# power.net
KiCad netlist of a schematic drawn in Altium Designer
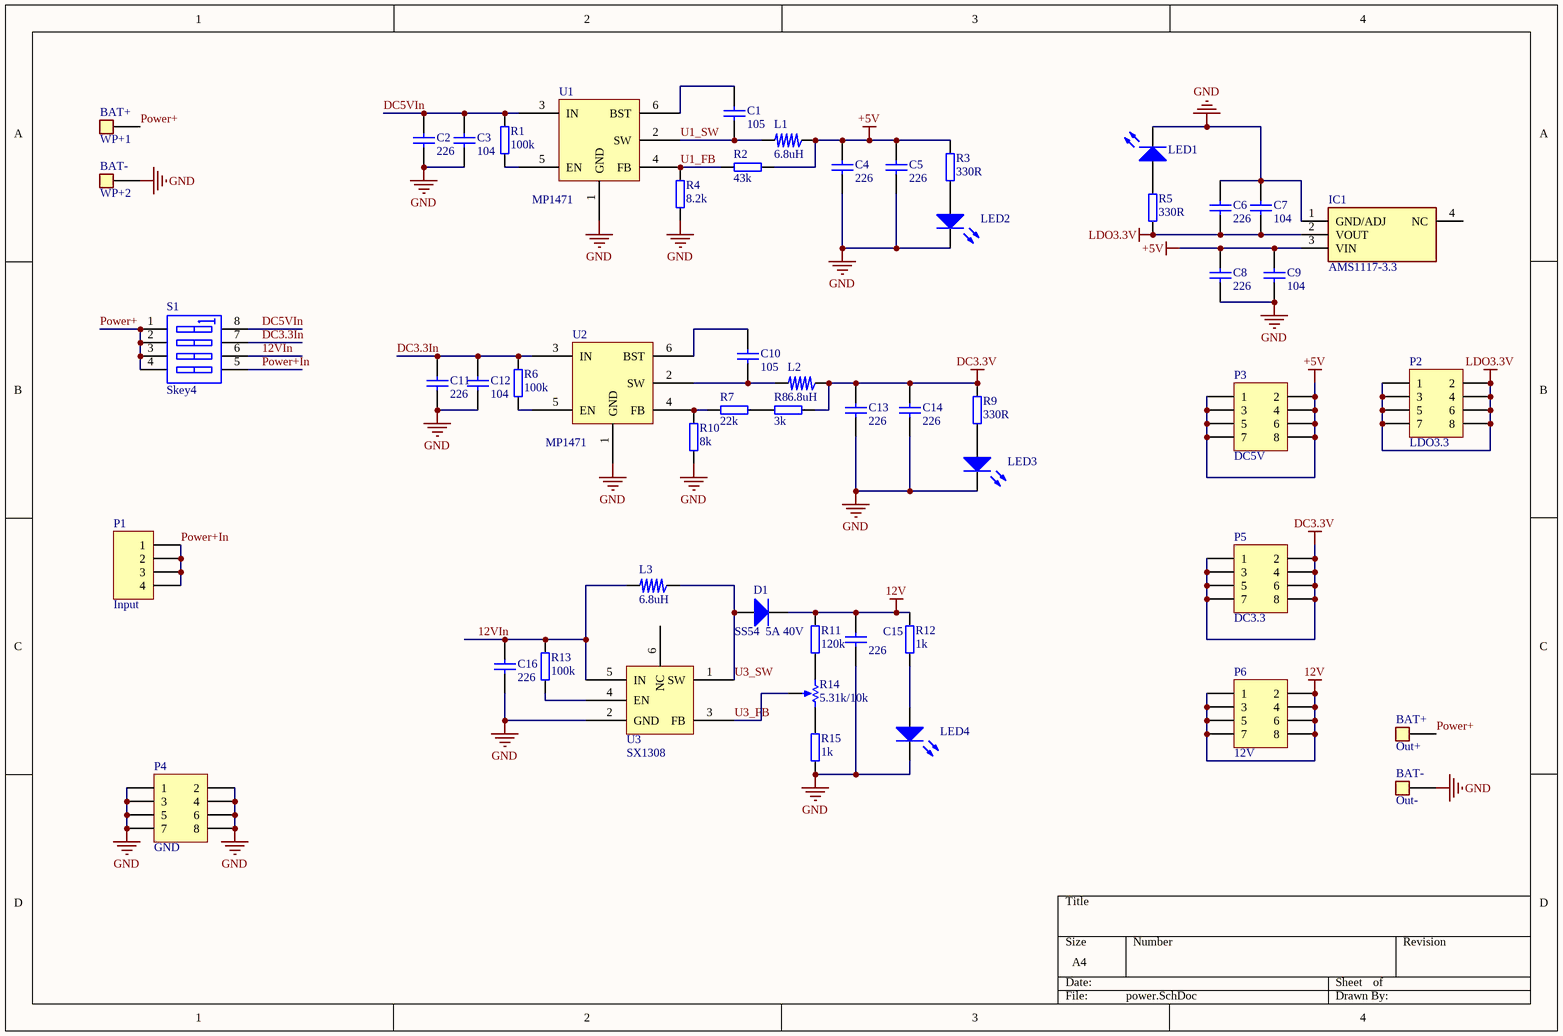
[diagram p0: power.SchDoc]

(export (version "E")
  (design (tool "Eeschema 10.0.6"))
  (components
    (comp (ref "C1")
      (value "105")
      (footprint "CAPC1608[0603]")
      (description "Chip Capacitor, PSpice Model")
      (fields
        (field (name "TOLERANCE") "Y5V")
        (field (name "VOLTAGE") "3V")
        (field (name "PUBLISHER") "Altium Limited")
      )
      (libsource (lib "!)Miscellaneous Integrated Library") (part "Cap Chip 1"))
    )
    (comp (ref "C2")
      (value "226")
      (footprint "CAPC1608[0603]")
      (description "Chip Capacitor, PSpice Model")
      (fields
        (field (name "TOLERANCE") "Y5V")
        (field (name "VOLTAGE") "3V")
        (field (name "PUBLISHER") "Altium Limited")
      )
      (libsource (lib "!)Miscellaneous Integrated Library") (part "Cap Chip 1"))
    )
    (comp (ref "C3")
      (value "104")
      (footprint "CAPC1608[0603]")
      (description "Chip Capacitor, PSpice Model")
      (fields
        (field (name "TOLERANCE") "Y5V")
        (field (name "VOLTAGE") "3V")
        (field (name "PUBLISHER") "Altium Limited")
      )
      (libsource (lib "!)Miscellaneous Integrated Library") (part "Cap Chip 1"))
    )
    (comp (ref "C4")
      (value "226")
      (footprint "CAPC1608[0603]")
      (description "Chip Capacitor, PSpice Model")
      (fields
        (field (name "TOLERANCE") "Y5V")
        (field (name "VOLTAGE") "3V")
        (field (name "PUBLISHER") "Altium Limited")
      )
      (libsource (lib "!)Miscellaneous Integrated Library") (part "Cap Chip 1"))
    )
    (comp (ref "C5")
      (value "226")
      (footprint "CAPC1608[0603]")
      (description "Chip Capacitor, PSpice Model")
      (fields
        (field (name "TOLERANCE") "Y5V")
        (field (name "VOLTAGE") "3V")
        (field (name "PUBLISHER") "Altium Limited")
      )
      (libsource (lib "!)Miscellaneous Integrated Library") (part "Cap Chip 1"))
    )
    (comp (ref "C6")
      (value "226")
      (footprint "CAPC1608[0603]")
      (description "Chip Capacitor, PSpice Model")
      (fields
        (field (name "TOLERANCE") "Y5V")
        (field (name "VOLTAGE") "3V")
        (field (name "PUBLISHER") "Altium Limited")
      )
      (libsource (lib "!)Miscellaneous Integrated Library") (part "Cap Chip 1"))
    )
    (comp (ref "C7")
      (value "104")
      (footprint "CAPC1608[0603]")
      (description "Chip Capacitor, PSpice Model")
      (fields
        (field (name "TOLERANCE") "Y5V")
        (field (name "VOLTAGE") "3V")
        (field (name "PUBLISHER") "Altium Limited")
      )
      (libsource (lib "!)Miscellaneous Integrated Library") (part "Cap Chip 1"))
    )
    (comp (ref "C8")
      (value "226")
      (footprint "CAPC1608[0603]")
      (description "Chip Capacitor, PSpice Model")
      (fields
        (field (name "TOLERANCE") "Y5V")
        (field (name "VOLTAGE") "3V")
        (field (name "PUBLISHER") "Altium Limited")
      )
      (libsource (lib "!)Miscellaneous Integrated Library") (part "Cap Chip 1"))
    )
    (comp (ref "C9")
      (value "104")
      (footprint "CAPC1608[0603]")
      (description "Chip Capacitor, PSpice Model")
      (fields
        (field (name "TOLERANCE") "Y5V")
        (field (name "VOLTAGE") "3V")
        (field (name "PUBLISHER") "Altium Limited")
      )
      (libsource (lib "!)Miscellaneous Integrated Library") (part "Cap Chip 1"))
    )
    (comp (ref "C10")
      (value "105")
      (footprint "CAPC1608[0603]")
      (description "Chip Capacitor, PSpice Model")
      (fields
        (field (name "TOLERANCE") "Y5V")
        (field (name "VOLTAGE") "3V")
        (field (name "PUBLISHER") "Altium Limited")
      )
      (libsource (lib "!)Miscellaneous Integrated Library") (part "Cap Chip 1"))
    )
    (comp (ref "C11")
      (value "226")
      (footprint "CAPC1608[0603]")
      (description "Chip Capacitor, PSpice Model")
      (fields
        (field (name "TOLERANCE") "Y5V")
        (field (name "VOLTAGE") "3V")
        (field (name "PUBLISHER") "Altium Limited")
      )
      (libsource (lib "!)Miscellaneous Integrated Library") (part "Cap Chip 1"))
    )
    (comp (ref "C12")
      (value "104")
      (footprint "CAPC1608[0603]")
      (description "Chip Capacitor, PSpice Model")
      (fields
        (field (name "TOLERANCE") "Y5V")
        (field (name "VOLTAGE") "3V")
        (field (name "PUBLISHER") "Altium Limited")
      )
      (libsource (lib "!)Miscellaneous Integrated Library") (part "Cap Chip 1"))
    )
    (comp (ref "C13")
      (value "226")
      (footprint "CAPC1608[0603]")
      (description "Chip Capacitor, PSpice Model")
      (fields
        (field (name "TOLERANCE") "Y5V")
        (field (name "VOLTAGE") "3V")
        (field (name "PUBLISHER") "Altium Limited")
      )
      (libsource (lib "!)Miscellaneous Integrated Library") (part "Cap Chip 1"))
    )
    (comp (ref "C14")
      (value "226")
      (footprint "CAPC1608[0603]")
      (description "Chip Capacitor, PSpice Model")
      (fields
        (field (name "TOLERANCE") "Y5V")
        (field (name "VOLTAGE") "3V")
        (field (name "PUBLISHER") "Altium Limited")
      )
      (libsource (lib "!)Miscellaneous Integrated Library") (part "Cap Chip 1"))
    )
    (comp (ref "C15")
      (value "226")
      (footprint "CAPC1608[0603]")
      (description "Chip Capacitor, PSpice Model")
      (fields
        (field (name "TOLERANCE") "Y5V")
        (field (name "VOLTAGE") "3V")
        (field (name "PUBLISHER") "Altium Limited")
      )
      (libsource (lib "!)Miscellaneous Integrated Library") (part "Cap Chip 1"))
    )
    (comp (ref "C16")
      (value "226")
      (footprint "CAPC1608[0603]")
      (description "Chip Capacitor, PSpice Model")
      (fields
        (field (name "TOLERANCE") "Y5V")
        (field (name "VOLTAGE") "3V")
        (field (name "PUBLISHER") "Altium Limited")
      )
      (libsource (lib "!)Miscellaneous Integrated Library") (part "Cap Chip 1"))
    )
    (comp (ref "D1")
      (value "SS54  5A 40V")
      (footprint "SMA[DO-214AC]")
      (description "Molded Diode")
      (fields
        (field (name "PARTNUMBER") "SS54  5A 40V")
        (field (name "VOLTAGE") "5A40V")
        (field (name "PUBLISHER") "Altium Limited")
      )
      (libsource (lib "!)Miscellaneous Integrated Library") (part "Diode SMx"))
    )
    (comp (ref "IC1")
      (value "AMS1117-3.3")
      (footprint "SOT229P700X180-4N")
      (description "Integrated Circuit")
      (libsource (lib "SamacSys") (part "AMS1117-3.3"))
    )
    (comp (ref "L1") (value "6.8uH") (footprint "WHC0420") (libsource (lib "BuildDev") (part "L")))
    (comp (ref "L2") (value "6.8uH") (footprint "WHC0420") (libsource (lib "BuildDev") (part "L")))
    (comp (ref "L3") (value "6.8uH") (footprint "WHC0420") (libsource (lib "BuildDev") (part "L")))
    (comp (ref "LED1")
      (value "Red")
      (footprint "LEDC1608(0603)")
      (description "Typical Chip LED")
      (fields (field (name "PUBLISHER") "Altium Limited"))
      (libsource (lib "!)Miscellaneous Integrated Library") (part "LED Chip"))
    )
    (comp (ref "LED2")
      (value "Red")
      (footprint "LEDC1608(0603)")
      (description "Typical Chip LED")
      (fields (field (name "PUBLISHER") "Altium Limited"))
      (libsource (lib "!)Miscellaneous Integrated Library") (part "LED Chip"))
    )
    (comp (ref "LED3")
      (value "Red")
      (footprint "LEDC1608(0603)")
      (description "Typical Chip LED")
      (fields (field (name "PUBLISHER") "Altium Limited"))
      (libsource (lib "!)Miscellaneous Integrated Library") (part "LED Chip"))
    )
    (comp (ref "LED4")
      (value "Red")
      (footprint "LEDC1608(0603)")
      (description "Typical Chip LED")
      (fields (field (name "PUBLISHER") "Altium Limited"))
      (libsource (lib "!)Miscellaneous Integrated Library") (part "LED Chip"))
    )
    (comp (ref "Out+")
      (value "BAT+")
      (footprint "WirePadSingleSide")
      (description "Wire soldering pad.")
      (libsource (lib "!)Miscellaneous Integrated Library") (part "Wire Pad"))
    )
    (comp (ref "Out-")
      (value "BAT-")
      (footprint "WirePadSingleSide")
      (description "Wire soldering pad.")
      (libsource (lib "!)Miscellaneous Integrated Library") (part "Wire Pad"))
    )
    (comp (ref "P1")
      (value "Input")
      (footprint "HDR1X4")
      (description "Header, 4-Pin")
      (fields (field (name "PUBLISHER") "Altium Limited"))
      (libsource (lib "!)Miscellaneous Integrated Library") (part "Header 4"))
    )
    (comp (ref "P2")
      (value "LDO3.3")
      (footprint "HDR2X4")
      (description "Header, 4-Pin, Dual row")
      (fields (field (name "PUBLISHER") "Altium Limited"))
      (libsource (lib "!)Miscellaneous Integrated Library") (part "Header 4X2"))
    )
    (comp (ref "P3")
      (value "DC5V")
      (footprint "HDR2X4")
      (description "Header, 4-Pin, Dual row")
      (fields (field (name "PUBLISHER") "Altium Limited"))
      (libsource (lib "!)Miscellaneous Integrated Library") (part "Header 4X2"))
    )
    (comp (ref "P4")
      (value "GND")
      (footprint "HDR2X4")
      (description "Header, 4-Pin, Dual row")
      (fields (field (name "PUBLISHER") "Altium Limited"))
      (libsource (lib "!)Miscellaneous Integrated Library") (part "Header 4X2"))
    )
    (comp (ref "P5")
      (value "DC3.3")
      (footprint "HDR2X4")
      (description "Header, 4-Pin, Dual row")
      (fields (field (name "PUBLISHER") "Altium Limited"))
      (libsource (lib "!)Miscellaneous Integrated Library") (part "Header 4X2"))
    )
    (comp (ref "P6")
      (value "12V")
      (footprint "HDR2X4")
      (description "Header, 4-Pin, Dual row")
      (fields (field (name "PUBLISHER") "Altium Limited"))
      (libsource (lib "!)Miscellaneous Integrated Library") (part "Header 4X2"))
    )
    (comp (ref "R1")
      (value "100k")
      (footprint "RESC1608[0603]")
      (description "Chip Resistor, PSpice Model, IPC PCB Library Drawing")
      (fields (field (name "TOLERANCE") "5%") (field (name "PUBLISHER") "Altium Limited"))
      (libsource (lib "!)Miscellaneous Integrated Library") (part "Res Chip 2p 1"))
    )
    (comp (ref "R2")
      (value "43k")
      (footprint "RESC1608[0603]")
      (description "Chip Resistor, PSpice Model, IPC PCB Library Drawing")
      (fields (field (name "TOLERANCE") "5%") (field (name "PUBLISHER") "Altium Limited"))
      (libsource (lib "!)Miscellaneous Integrated Library") (part "Res Chip 2p 1"))
    )
    (comp (ref "R3")
      (value "330R")
      (footprint "RESC1608[0603]")
      (description "Chip Resistor, PSpice Model, IPC PCB Library Drawing")
      (fields (field (name "TOLERANCE") "5%") (field (name "PUBLISHER") "Altium Limited"))
      (libsource (lib "!)Miscellaneous Integrated Library") (part "Res Chip 2p 1"))
    )
    (comp (ref "R4")
      (value "8.2k")
      (footprint "RESC1608[0603]")
      (description "Chip Resistor, PSpice Model, IPC PCB Library Drawing")
      (fields (field (name "TOLERANCE") "5%") (field (name "PUBLISHER") "Altium Limited"))
      (libsource (lib "!)Miscellaneous Integrated Library") (part "Res Chip 2p 1"))
    )
    (comp (ref "R5")
      (value "330R")
      (footprint "RESC1608[0603]")
      (description "Chip Resistor, PSpice Model, IPC PCB Library Drawing")
      (fields (field (name "TOLERANCE") "5%") (field (name "PUBLISHER") "Altium Limited"))
      (libsource (lib "!)Miscellaneous Integrated Library") (part "Res Chip 2p 1"))
    )
    (comp (ref "R6")
      (value "100k")
      (footprint "RESC1608[0603]")
      (description "Chip Resistor, PSpice Model, IPC PCB Library Drawing")
      (fields (field (name "TOLERANCE") "5%") (field (name "PUBLISHER") "Altium Limited"))
      (libsource (lib "!)Miscellaneous Integrated Library") (part "Res Chip 2p 1"))
    )
    (comp (ref "R7")
      (value "22k")
      (footprint "RESC1608[0603]")
      (description "Chip Resistor, PSpice Model, IPC PCB Library Drawing")
      (fields (field (name "TOLERANCE") "5%") (field (name "PUBLISHER") "Altium Limited"))
      (libsource (lib "!)Miscellaneous Integrated Library") (part "Res Chip 2p 1"))
    )
    (comp (ref "R8")
      (value "3k")
      (footprint "RESC1608[0603]")
      (description "Chip Resistor, PSpice Model, IPC PCB Library Drawing")
      (fields (field (name "TOLERANCE") "5%") (field (name "PUBLISHER") "Altium Limited"))
      (libsource (lib "!)Miscellaneous Integrated Library") (part "Res Chip 2p 1"))
    )
    (comp (ref "R9")
      (value "330R")
      (footprint "RESC1608[0603]")
      (description "Chip Resistor, PSpice Model, IPC PCB Library Drawing")
      (fields (field (name "TOLERANCE") "5%") (field (name "PUBLISHER") "Altium Limited"))
      (libsource (lib "!)Miscellaneous Integrated Library") (part "Res Chip 2p 1"))
    )
    (comp (ref "R10")
      (value "8k")
      (footprint "RESC1608[0603]")
      (description "Chip Resistor, PSpice Model, IPC PCB Library Drawing")
      (fields (field (name "TOLERANCE") "5%") (field (name "PUBLISHER") "Altium Limited"))
      (libsource (lib "!)Miscellaneous Integrated Library") (part "Res Chip 2p 1"))
    )
    (comp (ref "R11")
      (value "120k")
      (footprint "RESC1608[0603]")
      (description "Chip Resistor, PSpice Model, IPC PCB Library Drawing")
      (fields (field (name "TOLERANCE") "5%") (field (name "PUBLISHER") "Altium Limited"))
      (libsource (lib "!)Miscellaneous Integrated Library") (part "Res Chip 2p 1"))
    )
    (comp (ref "R12")
      (value "1k")
      (footprint "RESC1608[0603]")
      (description "Chip Resistor, PSpice Model, IPC PCB Library Drawing")
      (fields (field (name "TOLERANCE") "5%") (field (name "PUBLISHER") "Altium Limited"))
      (libsource (lib "!)Miscellaneous Integrated Library") (part "Res Chip 2p 1"))
    )
    (comp (ref "R13")
      (value "100k")
      (footprint "RESC1608[0603]")
      (description "Chip Resistor, PSpice Model, IPC PCB Library Drawing")
      (fields (field (name "TOLERANCE") "5%") (field (name "PUBLISHER") "Altium Limited"))
      (libsource (lib "!)Miscellaneous Integrated Library") (part "Res Chip 2p 1"))
    )
    (comp (ref "R14")
      (value "5.31k/10k")
      (footprint "Rhostat2")
      (libsource (lib "BuildDev") (part "Rhostat"))
    )
    (comp (ref "R15")
      (value "1k")
      (footprint "RESC1608[0603]")
      (description "Chip Resistor, PSpice Model, IPC PCB Library Drawing")
      (fields (field (name "TOLERANCE") "5%") (field (name "PUBLISHER") "Altium Limited"))
      (libsource (lib "!)Miscellaneous Integrated Library") (part "Res Chip 2p 1"))
    )
    (comp (ref "S1") (value "Skey4") (footprint "Skey4") (libsource (lib "BuildDev") (part "Skey4")))
    (comp (ref "U1")
      (value "MP1471")
      (footprint "TSOT23-6")
      (description "4.7v-16V Input\r\n16V3A\r\n500K")
      (libsource (lib "BuildDev") (part "MP1471"))
    )
    (comp (ref "U2")
      (value "MP1471")
      (footprint "TSOT23-6")
      (description "4.7v-16V Input\r\n16V3A\r\n500K")
      (libsource (lib "BuildDev") (part "MP1471"))
    )
    (comp (ref "U3")
      (value "SX1308")
      (footprint "SOT23-6")
      (description "boost\r\n1.2MHz\r\n2V-24V input\r\nup to 28V Output")
      (libsource (lib "BuildDev") (part "SX1308"))
    )
    (comp (ref "WP+1")
      (value "BAT+")
      (footprint "WirePadSingleSide")
      (description "Wire soldering pad.")
      (libsource (lib "!)Miscellaneous Integrated Library") (part "Wire Pad"))
    )
    (comp (ref "WP+2")
      (value "BAT-")
      (footprint "WirePadSingleSide")
      (description "Wire soldering pad.")
      (libsource (lib "!)Miscellaneous Integrated Library") (part "Wire Pad"))
    )
  )
  (nets
    (net (code "1") (name "+5V") (class "Default")
      (node (ref "C4") (pin "1") (pinfunction "1_1") (pintype "passive"))
      (node (ref "C5") (pin "1") (pinfunction "1_1") (pintype "passive"))
      (node (ref "C8") (pin "1") (pinfunction "1_1") (pintype "passive"))
      (node (ref "C9") (pin "1") (pinfunction "1_1") (pintype "passive"))
      (node (ref "IC1") (pin "3") (pinfunction "VIN_3") (pintype "passive"))
      (node (ref "L1") (pin "1") (pinfunction "1_1") (pintype "passive"))
      (node (ref "P3") (pin "1") (pinfunction "1_1") (pintype "passive"))
      (node (ref "P3") (pin "2") (pinfunction "2_2") (pintype "passive"))
      (node (ref "P3") (pin "3") (pinfunction "3_3") (pintype "passive"))
      (node (ref "P3") (pin "4") (pinfunction "4_4") (pintype "passive"))
      (node (ref "P3") (pin "5") (pinfunction "5_5") (pintype "passive"))
      (node (ref "P3") (pin "6") (pinfunction "6_6") (pintype "passive"))
      (node (ref "P3") (pin "7") (pinfunction "7_7") (pintype "passive"))
      (node (ref "P3") (pin "8") (pinfunction "8_8") (pintype "passive"))
      (node (ref "R2") (pin "2") (pinfunction "2_2") (pintype "passive"))
      (node (ref "R3") (pin "2") (pinfunction "2_2") (pintype "passive"))
    )
    (net (code "2") (name "/12VIn") (class "Default")
      (node (ref "C16") (pin "1") (pinfunction "1_1") (pintype "passive"))
      (node (ref "L3") (pin "2") (pinfunction "2_2") (pintype "passive"))
      (node (ref "R13") (pin "1") (pinfunction "1_1") (pintype "passive"))
      (node (ref "S1") (pin "6") (pinfunction "B3_6") (pintype "passive"))
      (node (ref "U3") (pin "5") (pinfunction "IN_5") (pintype "passive"))
    )
    (net (code "3") (name "/DC3.3In") (class "Default")
      (node (ref "C11") (pin "1") (pinfunction "1_1") (pintype "passive"))
      (node (ref "C12") (pin "1") (pinfunction "1_1") (pintype "passive"))
      (node (ref "R6") (pin "1") (pinfunction "1_1") (pintype "passive"))
      (node (ref "S1") (pin "7") (pinfunction "B2_7") (pintype "passive"))
      (node (ref "U2") (pin "3") (pinfunction "IN_3") (pintype "passive"))
    )
    (net (code "4") (name "/DC5VIn") (class "Default")
      (node (ref "C2") (pin "1") (pinfunction "1_1") (pintype "passive"))
      (node (ref "C3") (pin "1") (pinfunction "1_1") (pintype "passive"))
      (node (ref "R1") (pin "1") (pinfunction "1_1") (pintype "passive"))
      (node (ref "S1") (pin "8") (pinfunction "B1_8") (pintype "passive"))
      (node (ref "U1") (pin "3") (pinfunction "IN_3") (pintype "passive"))
    )
    (net (code "5") (name "/Power+") (class "Default")
      (node (ref "Out+") (pin "1") (pinfunction "0_1") (pintype "passive"))
      (node (ref "S1") (pin "1") (pinfunction "A1_1") (pintype "passive"))
      (node (ref "S1") (pin "2") (pinfunction "A2_2") (pintype "passive"))
      (node (ref "S1") (pin "3") (pinfunction "A3_3") (pintype "passive"))
      (node (ref "S1") (pin "4") (pinfunction "A4_4") (pintype "passive"))
      (node (ref "WP+1") (pin "1") (pinfunction "0_1") (pintype "passive"))
    )
    (net (code "6") (name "/Power+In") (class "Default")
      (node (ref "P1") (pin "1") (pinfunction "1_1") (pintype "passive"))
      (node (ref "P1") (pin "2") (pinfunction "2_2") (pintype "passive"))
      (node (ref "P1") (pin "3") (pinfunction "3_3") (pintype "passive"))
      (node (ref "P1") (pin "4") (pinfunction "4_4") (pintype "passive"))
      (node (ref "S1") (pin "5") (pinfunction "B4_5") (pintype "passive"))
    )
    (net (code "7") (name "/U1_FB") (class "Default")
      (node (ref "R2") (pin "1") (pinfunction "1_1") (pintype "passive"))
      (node (ref "R4") (pin "1") (pinfunction "1_1") (pintype "passive"))
      (node (ref "U1") (pin "4") (pinfunction "FB_4") (pintype "passive"))
    )
    (net (code "8") (name "/U1_SW") (class "Default")
      (node (ref "C1") (pin "2") (pinfunction "2_2") (pintype "passive"))
      (node (ref "L1") (pin "2") (pinfunction "2_2") (pintype "passive"))
      (node (ref "U1") (pin "2") (pinfunction "SW_2") (pintype "passive"))
    )
    (net (code "9") (name "/U3_FB") (class "Default")
      (node (ref "R14") (pin "3") (pinfunction "TAP_3") (pintype "passive"))
      (node (ref "U3") (pin "3") (pinfunction "FB_3") (pintype "passive"))
    )
    (net (code "10") (name "/U3_SW") (class "Default")
      (node (ref "D1") (pin "A") (pinfunction "A_A") (pintype "passive"))
      (node (ref "L3") (pin "1") (pinfunction "1_1") (pintype "passive"))
      (node (ref "U3") (pin "1") (pinfunction "SW_1") (pintype "passive"))
    )
    (net (code "11") (name "12V") (class "Default")
      (node (ref "C15") (pin "1") (pinfunction "1_1") (pintype "passive"))
      (node (ref "D1") (pin "K") (pinfunction "K_K") (pintype "passive"))
      (node (ref "P6") (pin "1") (pinfunction "1_1") (pintype "passive"))
      (node (ref "P6") (pin "2") (pinfunction "2_2") (pintype "passive"))
      (node (ref "P6") (pin "3") (pinfunction "3_3") (pintype "passive"))
      (node (ref "P6") (pin "4") (pinfunction "4_4") (pintype "passive"))
      (node (ref "P6") (pin "5") (pinfunction "5_5") (pintype "passive"))
      (node (ref "P6") (pin "6") (pinfunction "6_6") (pintype "passive"))
      (node (ref "P6") (pin "7") (pinfunction "7_7") (pintype "passive"))
      (node (ref "P6") (pin "8") (pinfunction "8_8") (pintype "passive"))
      (node (ref "R11") (pin "2") (pinfunction "2_2") (pintype "passive"))
      (node (ref "R12") (pin "2") (pinfunction "2_2") (pintype "passive"))
    )
    (net (code "12") (name "DC3.3V") (class "Default")
      (node (ref "C13") (pin "1") (pinfunction "1_1") (pintype "passive"))
      (node (ref "C14") (pin "1") (pinfunction "1_1") (pintype "passive"))
      (node (ref "L2") (pin "1") (pinfunction "1_1") (pintype "passive"))
      (node (ref "P5") (pin "1") (pinfunction "1_1") (pintype "passive"))
      (node (ref "P5") (pin "2") (pinfunction "2_2") (pintype "passive"))
      (node (ref "P5") (pin "3") (pinfunction "3_3") (pintype "passive"))
      (node (ref "P5") (pin "4") (pinfunction "4_4") (pintype "passive"))
      (node (ref "P5") (pin "5") (pinfunction "5_5") (pintype "passive"))
      (node (ref "P5") (pin "6") (pinfunction "6_6") (pintype "passive"))
      (node (ref "P5") (pin "7") (pinfunction "7_7") (pintype "passive"))
      (node (ref "P5") (pin "8") (pinfunction "8_8") (pintype "passive"))
      (node (ref "R8") (pin "2") (pinfunction "2_2") (pintype "passive"))
      (node (ref "R9") (pin "2") (pinfunction "2_2") (pintype "passive"))
    )
    (net (code "13") (name "GND") (class "Default")
      (node (ref "C11") (pin "2") (pinfunction "2_2") (pintype "passive"))
      (node (ref "C12") (pin "2") (pinfunction "2_2") (pintype "passive"))
      (node (ref "C13") (pin "2") (pinfunction "2_2") (pintype "passive"))
      (node (ref "C14") (pin "2") (pinfunction "2_2") (pintype "passive"))
      (node (ref "C15") (pin "2") (pinfunction "2_2") (pintype "passive"))
      (node (ref "C16") (pin "2") (pinfunction "2_2") (pintype "passive"))
      (node (ref "C2") (pin "2") (pinfunction "2_2") (pintype "passive"))
      (node (ref "C3") (pin "2") (pinfunction "2_2") (pintype "passive"))
      (node (ref "C4") (pin "2") (pinfunction "2_2") (pintype "passive"))
      (node (ref "C5") (pin "2") (pinfunction "2_2") (pintype "passive"))
      (node (ref "C6") (pin "1") (pinfunction "1_1") (pintype "passive"))
      (node (ref "C7") (pin "1") (pinfunction "1_1") (pintype "passive"))
      (node (ref "C8") (pin "2") (pinfunction "2_2") (pintype "passive"))
      (node (ref "C9") (pin "2") (pinfunction "2_2") (pintype "passive"))
      (node (ref "IC1") (pin "1") (pinfunction "GND/ADJ_1") (pintype "passive"))
      (node (ref "LED1") (pin "C") (pinfunction "C_C") (pintype "passive"))
      (node (ref "LED2") (pin "C") (pinfunction "C_C") (pintype "passive"))
      (node (ref "LED3") (pin "C") (pinfunction "C_C") (pintype "passive"))
      (node (ref "LED4") (pin "C") (pinfunction "C_C") (pintype "passive"))
      (node (ref "Out-") (pin "1") (pinfunction "0_1") (pintype "passive"))
      (node (ref "P4") (pin "1") (pinfunction "1_1") (pintype "passive"))
      (node (ref "P4") (pin "2") (pinfunction "2_2") (pintype "passive"))
      (node (ref "P4") (pin "3") (pinfunction "3_3") (pintype "passive"))
      (node (ref "P4") (pin "4") (pinfunction "4_4") (pintype "passive"))
      (node (ref "P4") (pin "5") (pinfunction "5_5") (pintype "passive"))
      (node (ref "P4") (pin "6") (pinfunction "6_6") (pintype "passive"))
      (node (ref "P4") (pin "7") (pinfunction "7_7") (pintype "passive"))
      (node (ref "P4") (pin "8") (pinfunction "8_8") (pintype "passive"))
      (node (ref "R10") (pin "2") (pinfunction "2_2") (pintype "passive"))
      (node (ref "R15") (pin "1") (pinfunction "1_1") (pintype "passive"))
      (node (ref "R4") (pin "2") (pinfunction "2_2") (pintype "passive"))
      (node (ref "U1") (pin "1") (pinfunction "GND_1") (pintype "passive"))
      (node (ref "U2") (pin "1") (pinfunction "GND_1") (pintype "passive"))
      (node (ref "U3") (pin "2") (pinfunction "GND_2") (pintype "passive"))
      (node (ref "WP+2") (pin "1") (pinfunction "0_1") (pintype "passive"))
    )
    (net (code "14") (name "LDO3.3V") (class "Default")
      (node (ref "C6") (pin "2") (pinfunction "2_2") (pintype "passive"))
      (node (ref "C7") (pin "2") (pinfunction "2_2") (pintype "passive"))
      (node (ref "IC1") (pin "2") (pinfunction "VOUT_2") (pintype "passive"))
      (node (ref "P2") (pin "1") (pinfunction "1_1") (pintype "passive"))
      (node (ref "P2") (pin "2") (pinfunction "2_2") (pintype "passive"))
      (node (ref "P2") (pin "3") (pinfunction "3_3") (pintype "passive"))
      (node (ref "P2") (pin "4") (pinfunction "4_4") (pintype "passive"))
      (node (ref "P2") (pin "5") (pinfunction "5_5") (pintype "passive"))
      (node (ref "P2") (pin "6") (pinfunction "6_6") (pintype "passive"))
      (node (ref "P2") (pin "7") (pinfunction "7_7") (pintype "passive"))
      (node (ref "P2") (pin "8") (pinfunction "8_8") (pintype "passive"))
      (node (ref "R5") (pin "1") (pinfunction "1_1") (pintype "passive"))
    )
    (net (code "15") (name "Net-(LED1-PadA)") (class "Default")
      (node (ref "LED1") (pin "A") (pinfunction "A_A") (pintype "passive"))
      (node (ref "R5") (pin "2") (pinfunction "2_2") (pintype "passive"))
    )
    (net (code "16") (name "Net-(LED2-PadA)") (class "Default")
      (node (ref "LED2") (pin "A") (pinfunction "A_A") (pintype "passive"))
      (node (ref "R3") (pin "1") (pinfunction "1_1") (pintype "passive"))
    )
    (net (code "17") (name "Net-(LED3-PadA)") (class "Default")
      (node (ref "LED3") (pin "A") (pinfunction "A_A") (pintype "passive"))
      (node (ref "R9") (pin "1") (pinfunction "1_1") (pintype "passive"))
    )
    (net (code "18") (name "Net-(LED4-PadA)") (class "Default")
      (node (ref "LED4") (pin "A") (pinfunction "A_A") (pintype "passive"))
      (node (ref "R12") (pin "1") (pinfunction "1_1") (pintype "passive"))
    )
    (net (code "19") (name "Net-(R7-Pad2)") (class "Default")
      (node (ref "R7") (pin "2") (pinfunction "2_2") (pintype "passive"))
      (node (ref "R8") (pin "1") (pinfunction "1_1") (pintype "passive"))
    )
    (net (code "20") (name "Net-(R14-BOT)") (class "Default")
      (node (ref "R14") (pin "2") (pinfunction "BOT_2") (pintype "passive"))
      (node (ref "R15") (pin "2") (pinfunction "2_2") (pintype "passive"))
    )
    (net (code "21") (name "Net-(R14-TOP)") (class "Default")
      (node (ref "R11") (pin "1") (pinfunction "1_1") (pintype "passive"))
      (node (ref "R14") (pin "1") (pinfunction "TOP_1") (pintype "passive"))
    )
    (net (code "22") (name "Net-(U1-BST)") (class "Default")
      (node (ref "C1") (pin "1") (pinfunction "1_1") (pintype "passive"))
      (node (ref "U1") (pin "6") (pinfunction "BST_6") (pintype "passive"))
    )
    (net (code "23") (name "Net-(U1-EN)") (class "Default")
      (node (ref "R1") (pin "2") (pinfunction "2_2") (pintype "passive"))
      (node (ref "U1") (pin "5") (pinfunction "EN_5") (pintype "passive"))
    )
    (net (code "24") (name "Net-(U2-BST)") (class "Default")
      (node (ref "C10") (pin "1") (pinfunction "1_1") (pintype "passive"))
      (node (ref "U2") (pin "6") (pinfunction "BST_6") (pintype "passive"))
    )
    (net (code "25") (name "Net-(U2-EN)") (class "Default")
      (node (ref "R6") (pin "2") (pinfunction "2_2") (pintype "passive"))
      (node (ref "U2") (pin "5") (pinfunction "EN_5") (pintype "passive"))
    )
    (net (code "26") (name "Net-(U2-FB)") (class "Default")
      (node (ref "R10") (pin "1") (pinfunction "1_1") (pintype "passive"))
      (node (ref "R7") (pin "1") (pinfunction "1_1") (pintype "passive"))
      (node (ref "U2") (pin "4") (pinfunction "FB_4") (pintype "passive"))
    )
    (net (code "27") (name "Net-(U2-SW)") (class "Default")
      (node (ref "C10") (pin "2") (pinfunction "2_2") (pintype "passive"))
      (node (ref "L2") (pin "2") (pinfunction "2_2") (pintype "passive"))
      (node (ref "U2") (pin "2") (pinfunction "SW_2") (pintype "passive"))
    )
    (net (code "28") (name "Net-(U3-EN)") (class "Default")
      (node (ref "R13") (pin "2") (pinfunction "2_2") (pintype "passive"))
      (node (ref "U3") (pin "4") (pinfunction "EN_4") (pintype "passive"))
    )
    (net (code "29") (name "unconnected-(IC1-NC-Pad4)") (class "Default")
      (node (ref "IC1") (pin "4") (pinfunction "NC_4") (pintype "passive"))
    )
    (net (code "30") (name "unconnected-(U3-NC-Pad6)") (class "Default")
      (node (ref "U3") (pin "6") (pinfunction "NC_6") (pintype "passive"))
    )
  )
)
